# Commodore_KB_Tester.net
KiCad netlist of a schematic drawn in EAGLE
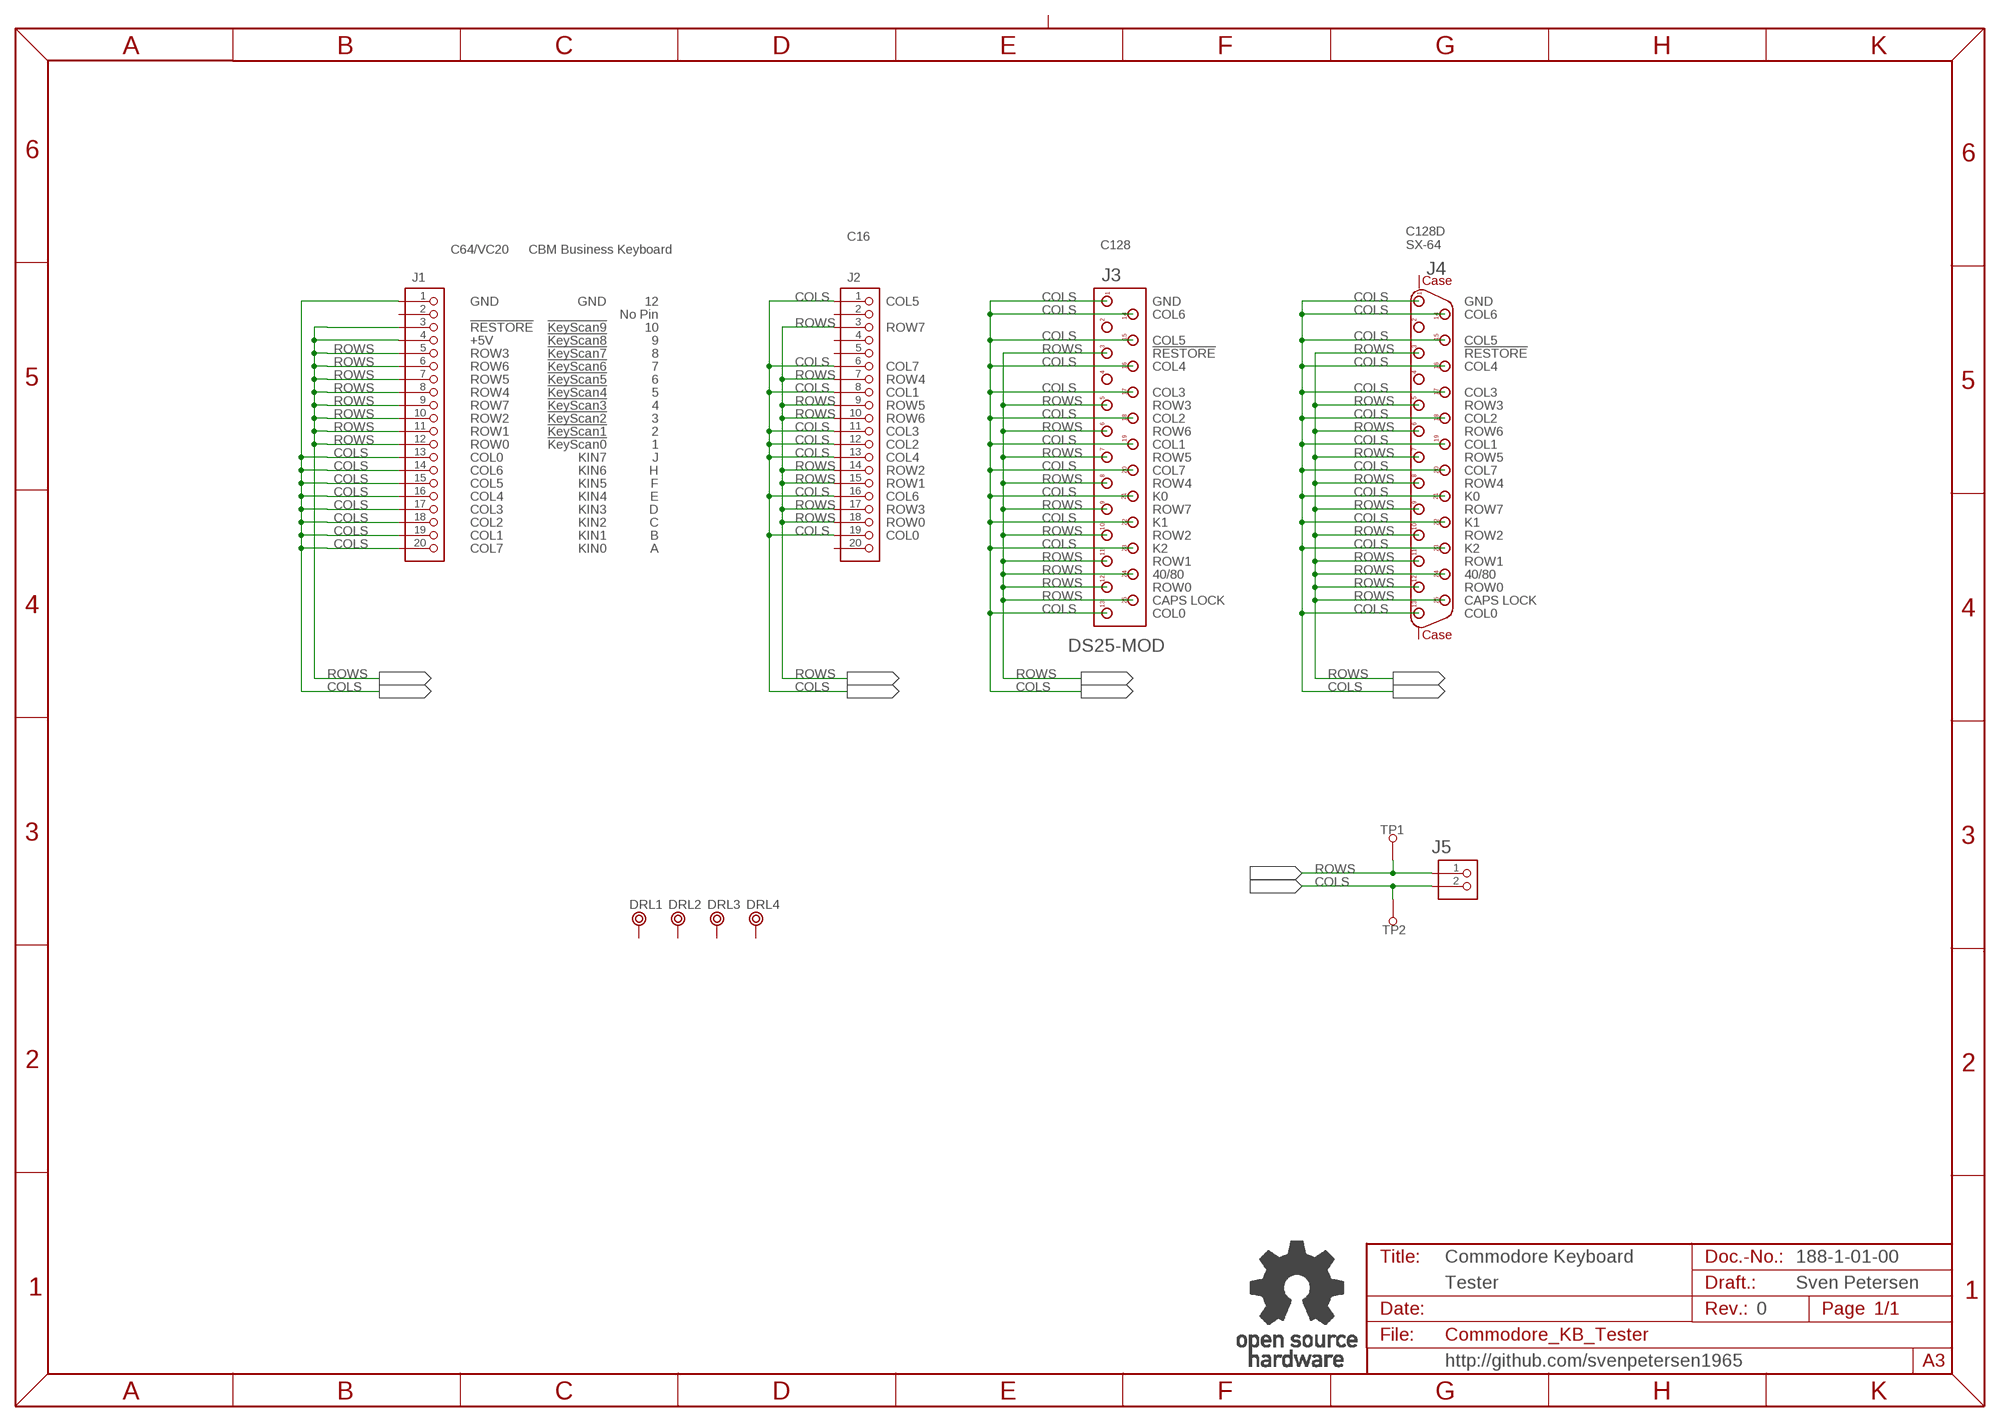
[diagram p0: schematic, sheet 1]

(export (version "E")
  (design (tool "Eeschema 10.0.6"))
  (components
    (comp (ref "DRL1")
      (value "BOHR3,5")
      (footprint "eagle-import:BOHR3,5")
      (libsource (lib "eagle-import") (part "BOHR3,5"))
    )
    (comp (ref "DRL2")
      (value "BOHR3,5")
      (footprint "eagle-import:BOHR3,5")
      (libsource (lib "eagle-import") (part "BOHR3,5"))
    )
    (comp (ref "DRL3")
      (value "BOHR3,5")
      (footprint "eagle-import:BOHR3,5")
      (libsource (lib "eagle-import") (part "BOHR3,5"))
    )
    (comp (ref "DRL4")
      (value "BOHR3,5")
      (footprint "eagle-import:BOHR3,5")
      (libsource (lib "eagle-import") (part "BOHR3,5"))
    )
    (comp (ref "J1")
      (value "PINHD-1X20")
      (footprint "eagle-import:1X20")
      (libsource (lib "eagle-import") (part "PINHD-1X20"))
    )
    (comp (ref "J2")
      (value "PINHD-1X20")
      (footprint "eagle-import:1X20")
      (libsource (lib "eagle-import") (part "PINHD-1X20"))
    )
    (comp (ref "J3")
      (value "DS25-MOD")
      (footprint "eagle-import:C128KB_HEADER")
      (libsource (lib "eagle-import") (part "C128_KBHEADER"))
    )
    (comp (ref "J4")
      (value "DS25F-V-CL")
      (footprint "eagle-import:DS25F-V")
      (libsource (lib "eagle-import") (part "DS25F-V-CL"))
    )
    (comp (ref "J5")
      (value "PINHD-1X2")
      (footprint "eagle-import:1X02")
      (libsource (lib "eagle-import") (part "PINHD-1X2"))
    )
    (comp (ref "TP1")
      (value "1,3/2,0")
      (footprint "eagle-import:1,3_2,0")
      (libsource (lib "eagle-import") (part "1,3/2,0"))
    )
    (comp (ref "TP2")
      (value "1,3/2,0")
      (footprint "eagle-import:1,3_2,0")
      (libsource (lib "eagle-import") (part "1,3/2,0"))
    )
    (comp (ref "U$12")
      (value "OPEN_SOURCE_HW")
      (footprint "eagle-import:OPENHW")
      (libsource (lib "eagle-import") (part "OPEN_SOURCE_HW"))
    )
  )
  (nets
    (net (code "1") (name "/COLS") (class "Default")
      (node (ref "J1") (pin "1") (pinfunction "1_1") (pintype "passive"))
      (node (ref "J1") (pin "13") (pinfunction "13_13") (pintype "passive"))
      (node (ref "J1") (pin "14") (pinfunction "14_14") (pintype "passive"))
      (node (ref "J1") (pin "15") (pinfunction "15_15") (pintype "passive"))
      (node (ref "J1") (pin "16") (pinfunction "16_16") (pintype "passive"))
      (node (ref "J1") (pin "17") (pinfunction "17_17") (pintype "passive"))
      (node (ref "J1") (pin "18") (pinfunction "18_18") (pintype "passive"))
      (node (ref "J1") (pin "19") (pinfunction "19_19") (pintype "passive"))
      (node (ref "J1") (pin "20") (pinfunction "20_20") (pintype "passive"))
      (node (ref "J2") (pin "1") (pinfunction "1_1") (pintype "passive"))
      (node (ref "J2") (pin "11") (pinfunction "11_11") (pintype "passive"))
      (node (ref "J2") (pin "12") (pinfunction "12_12") (pintype "passive"))
      (node (ref "J2") (pin "13") (pinfunction "13_13") (pintype "passive"))
      (node (ref "J2") (pin "16") (pinfunction "16_16") (pintype "passive"))
      (node (ref "J2") (pin "19") (pinfunction "19_19") (pintype "passive"))
      (node (ref "J2") (pin "6") (pinfunction "6_6") (pintype "passive"))
      (node (ref "J2") (pin "8") (pinfunction "8_8") (pintype "passive"))
      (node (ref "J3") (pin "1") (pinfunction "1_1") (pintype "passive"))
      (node (ref "J3") (pin "13") (pinfunction "13_13") (pintype "passive"))
      (node (ref "J3") (pin "14") (pinfunction "14_14") (pintype "passive"))
      (node (ref "J3") (pin "15") (pinfunction "15_15") (pintype "passive"))
      (node (ref "J3") (pin "16") (pinfunction "16_16") (pintype "passive"))
      (node (ref "J3") (pin "17") (pinfunction "17_17") (pintype "passive"))
      (node (ref "J3") (pin "18") (pinfunction "18_18") (pintype "passive"))
      (node (ref "J3") (pin "19") (pinfunction "19_19") (pintype "passive"))
      (node (ref "J3") (pin "20") (pinfunction "20_20") (pintype "passive"))
      (node (ref "J3") (pin "21") (pinfunction "21_21") (pintype "passive"))
      (node (ref "J3") (pin "22") (pinfunction "22_22") (pintype "passive"))
      (node (ref "J3") (pin "23") (pinfunction "23_23") (pintype "passive"))
      (node (ref "J4") (pin "1") (pinfunction "1_1") (pintype "passive"))
      (node (ref "J4") (pin "13") (pinfunction "13_13") (pintype "passive"))
      (node (ref "J4") (pin "14") (pinfunction "14_14") (pintype "passive"))
      (node (ref "J4") (pin "15") (pinfunction "15_15") (pintype "passive"))
      (node (ref "J4") (pin "16") (pinfunction "16_16") (pintype "passive"))
      (node (ref "J4") (pin "17") (pinfunction "17_17") (pintype "passive"))
      (node (ref "J4") (pin "18") (pinfunction "18_18") (pintype "passive"))
      (node (ref "J4") (pin "19") (pinfunction "19_19") (pintype "passive"))
      (node (ref "J4") (pin "20") (pinfunction "20_20") (pintype "passive"))
      (node (ref "J4") (pin "21") (pinfunction "21_21") (pintype "passive"))
      (node (ref "J4") (pin "22") (pinfunction "22_22") (pintype "passive"))
      (node (ref "J4") (pin "23") (pinfunction "23_23") (pintype "passive"))
      (node (ref "J5") (pin "2") (pinfunction "2_2") (pintype "passive"))
      (node (ref "TP2") (pin "1") (pinfunction "1_1") (pintype "passive"))
    )
    (net (code "2") (name "/ROWS") (class "Default")
      (node (ref "J1") (pin "10") (pinfunction "10_10") (pintype "passive"))
      (node (ref "J1") (pin "11") (pinfunction "11_11") (pintype "passive"))
      (node (ref "J1") (pin "12") (pinfunction "12_12") (pintype "passive"))
      (node (ref "J1") (pin "3") (pinfunction "3_3") (pintype "passive"))
      (node (ref "J1") (pin "4") (pinfunction "4_4") (pintype "passive"))
      (node (ref "J1") (pin "5") (pinfunction "5_5") (pintype "passive"))
      (node (ref "J1") (pin "6") (pinfunction "6_6") (pintype "passive"))
      (node (ref "J1") (pin "7") (pinfunction "7_7") (pintype "passive"))
      (node (ref "J1") (pin "8") (pinfunction "8_8") (pintype "passive"))
      (node (ref "J1") (pin "9") (pinfunction "9_9") (pintype "passive"))
      (node (ref "J2") (pin "10") (pinfunction "10_10") (pintype "passive"))
      (node (ref "J2") (pin "14") (pinfunction "14_14") (pintype "passive"))
      (node (ref "J2") (pin "15") (pinfunction "15_15") (pintype "passive"))
      (node (ref "J2") (pin "17") (pinfunction "17_17") (pintype "passive"))
      (node (ref "J2") (pin "18") (pinfunction "18_18") (pintype "passive"))
      (node (ref "J2") (pin "3") (pinfunction "3_3") (pintype "passive"))
      (node (ref "J2") (pin "7") (pinfunction "7_7") (pintype "passive"))
      (node (ref "J2") (pin "9") (pinfunction "9_9") (pintype "passive"))
      (node (ref "J3") (pin "10") (pinfunction "10_10") (pintype "passive"))
      (node (ref "J3") (pin "11") (pinfunction "11_11") (pintype "passive"))
      (node (ref "J3") (pin "12") (pinfunction "12_12") (pintype "passive"))
      (node (ref "J3") (pin "24") (pinfunction "24_24") (pintype "passive"))
      (node (ref "J3") (pin "25") (pinfunction "25_25") (pintype "passive"))
      (node (ref "J3") (pin "3") (pinfunction "3_3") (pintype "passive"))
      (node (ref "J3") (pin "5") (pinfunction "5_5") (pintype "passive"))
      (node (ref "J3") (pin "6") (pinfunction "6_6") (pintype "passive"))
      (node (ref "J3") (pin "7") (pinfunction "7_7") (pintype "passive"))
      (node (ref "J3") (pin "8") (pinfunction "8_8") (pintype "passive"))
      (node (ref "J3") (pin "9") (pinfunction "9_9") (pintype "passive"))
      (node (ref "J4") (pin "10") (pinfunction "10_10") (pintype "passive"))
      (node (ref "J4") (pin "11") (pinfunction "11_11") (pintype "passive"))
      (node (ref "J4") (pin "12") (pinfunction "12_12") (pintype "passive"))
      (node (ref "J4") (pin "24") (pinfunction "24_24") (pintype "passive"))
      (node (ref "J4") (pin "25") (pinfunction "25_25") (pintype "passive"))
      (node (ref "J4") (pin "3") (pinfunction "3_3") (pintype "passive"))
      (node (ref "J4") (pin "5") (pinfunction "5_5") (pintype "passive"))
      (node (ref "J4") (pin "6") (pinfunction "6_6") (pintype "passive"))
      (node (ref "J4") (pin "7") (pinfunction "7_7") (pintype "passive"))
      (node (ref "J4") (pin "8") (pinfunction "8_8") (pintype "passive"))
      (node (ref "J4") (pin "9") (pinfunction "9_9") (pintype "passive"))
      (node (ref "J5") (pin "1") (pinfunction "1_1") (pintype "passive"))
      (node (ref "TP1") (pin "1") (pinfunction "1_1") (pintype "passive"))
    )
    (net (code "3") (name "unconnected-(DRL1-PadP$1)") (class "Default")
      (node (ref "DRL1") (pin "P$1") (pinfunction "P$1_P$1") (pintype "passive"))
    )
    (net (code "4") (name "unconnected-(DRL2-PadP$1)") (class "Default")
      (node (ref "DRL2") (pin "P$1") (pinfunction "P$1_P$1") (pintype "passive"))
    )
    (net (code "5") (name "unconnected-(DRL3-PadP$1)") (class "Default")
      (node (ref "DRL3") (pin "P$1") (pinfunction "P$1_P$1") (pintype "passive"))
    )
    (net (code "6") (name "unconnected-(DRL4-PadP$1)") (class "Default")
      (node (ref "DRL4") (pin "P$1") (pinfunction "P$1_P$1") (pintype "passive"))
    )
    (net (code "7") (name "unconnected-(J1-Pad2)") (class "Default")
      (node (ref "J1") (pin "2") (pinfunction "2_2") (pintype "passive"))
    )
    (net (code "8") (name "unconnected-(J2-Pad2)") (class "Default")
      (node (ref "J2") (pin "2") (pinfunction "2_2") (pintype "passive"))
    )
    (net (code "9") (name "unconnected-(J2-Pad4)") (class "Default")
      (node (ref "J2") (pin "4") (pinfunction "4_4") (pintype "passive"))
    )
    (net (code "10") (name "unconnected-(J2-Pad5)") (class "Default")
      (node (ref "J2") (pin "5") (pinfunction "5_5") (pintype "passive"))
    )
    (net (code "11") (name "unconnected-(J2-Pad20)") (class "Default")
      (node (ref "J2") (pin "20") (pinfunction "20_20") (pintype "passive"))
    )
    (net (code "12") (name "unconnected-(J3-Pad2)") (class "Default")
      (node (ref "J3") (pin "2") (pinfunction "2_2") (pintype "passive"))
    )
    (net (code "13") (name "unconnected-(J3-Pad4)") (class "Default")
      (node (ref "J3") (pin "4") (pinfunction "4_4") (pintype "passive"))
    )
    (net (code "14") (name "unconnected-(J4-CL1-PadPE1)") (class "Default")
      (node (ref "J4") (pin "PE1") (pinfunction "CL1_PE1") (pintype "bidirectional"))
    )
    (net (code "15") (name "unconnected-(J4-CL2-PadPE2)") (class "Default")
      (node (ref "J4") (pin "PE2") (pinfunction "CL2_PE2") (pintype "bidirectional"))
    )
    (net (code "16") (name "unconnected-(J4-Pad2)") (class "Default")
      (node (ref "J4") (pin "2") (pinfunction "2_2") (pintype "passive"))
    )
    (net (code "17") (name "unconnected-(J4-Pad4)") (class "Default")
      (node (ref "J4") (pin "4") (pinfunction "4_4") (pintype "passive"))
    )
  )
)
